# Spectacle_LED_Control_Board.net
KiCad netlist of a schematic drawn in EAGLE
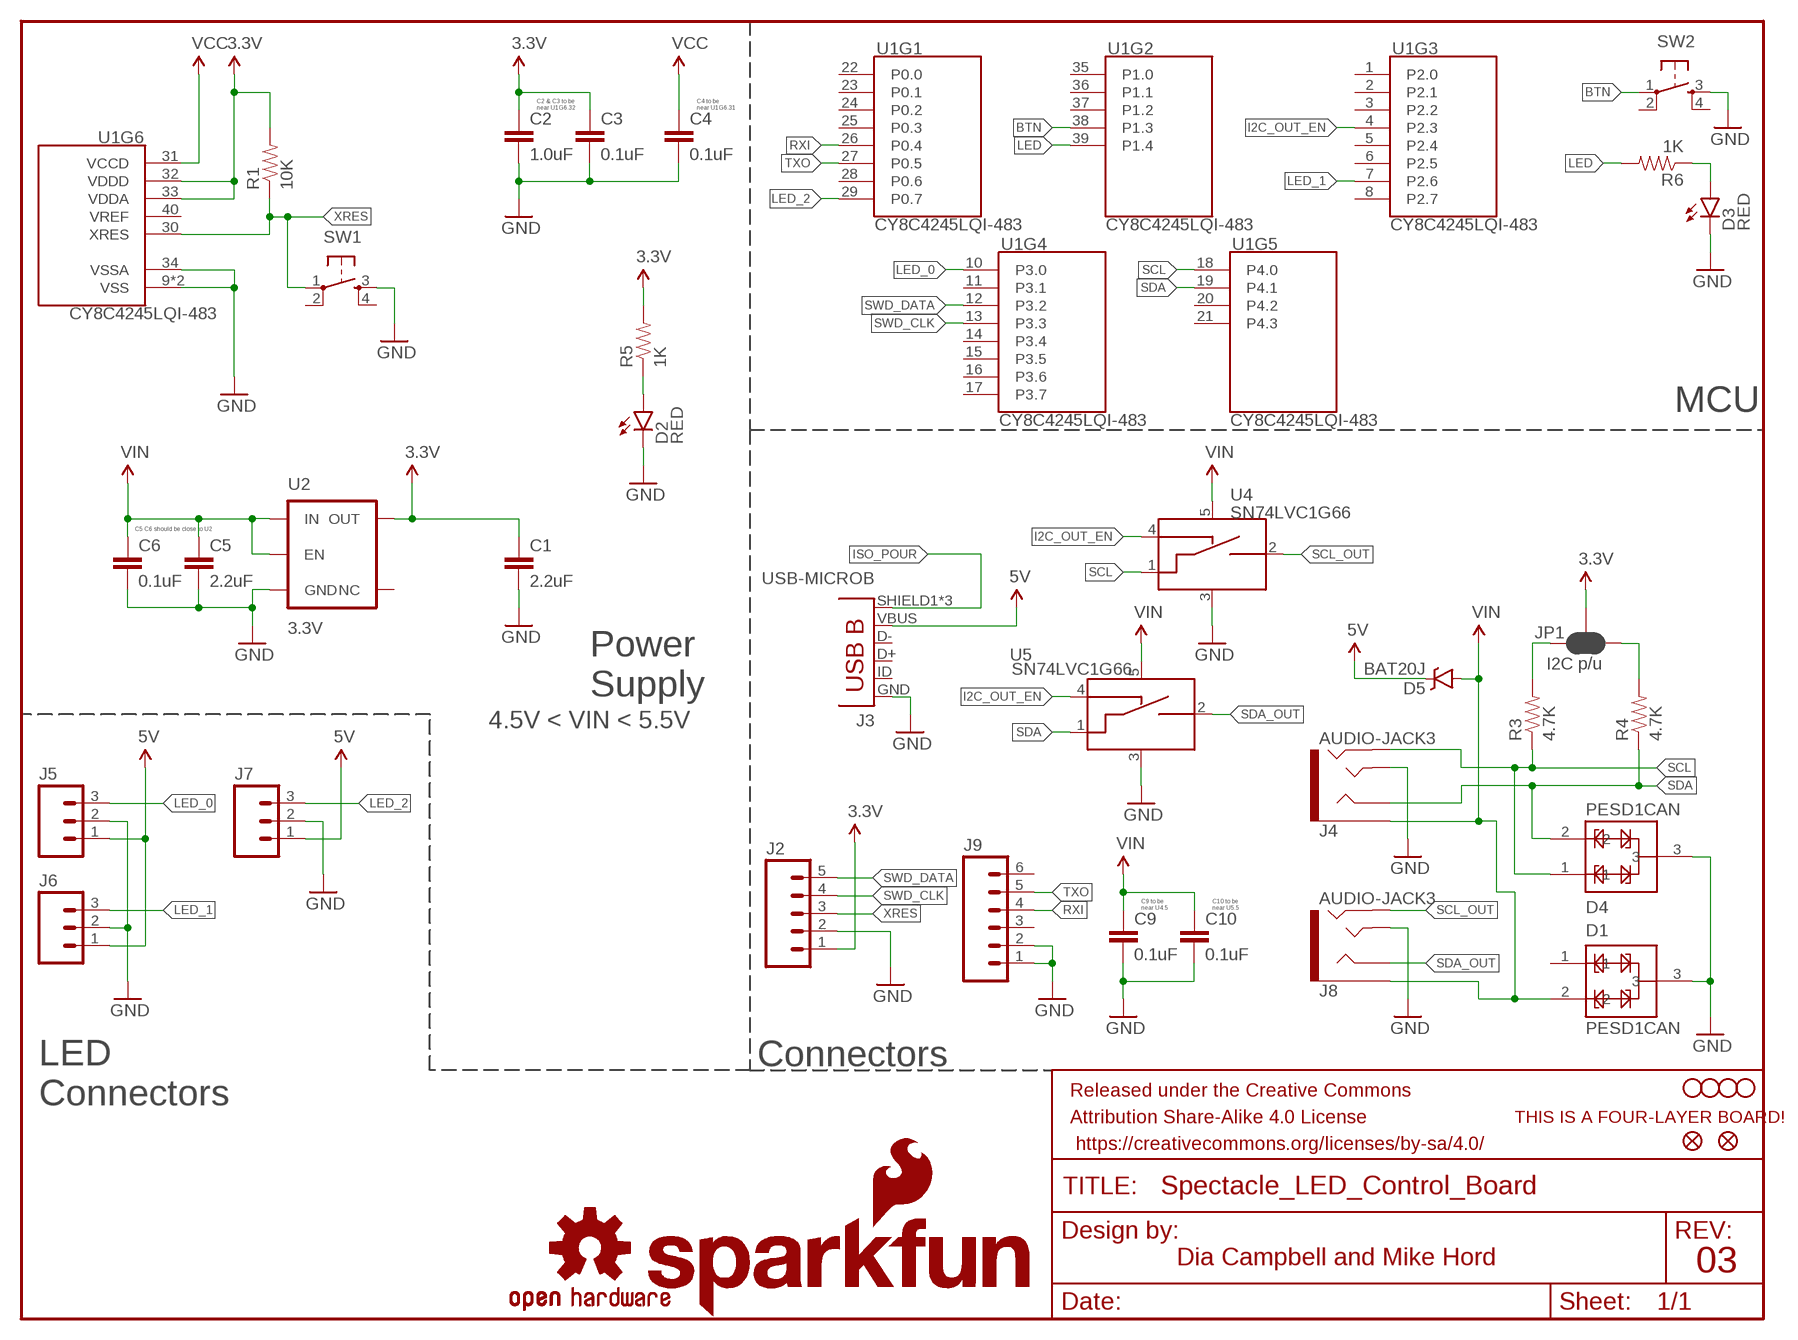
[diagram p0: schematic, sheet 1]

(export (version "E")
  (design (tool "Eeschema 10.0.6"))
  (components
    (comp (ref "C1")
      (value "2.2uF")
      (footprint "eagle-import:0603-CAP")
      (libsource (lib "eagle-import") (part "2.2UF-10V-20%(0603)"))
    )
    (comp (ref "C2")
      (value "1.0uF")
      (footprint "eagle-import:0402-CAP")
      (libsource (lib "eagle-import") (part "1.0UF-16V-10%(0402)"))
    )
    (comp (ref "C3")
      (value "0.1uF")
      (footprint "eagle-import:0402-CAP")
      (libsource (lib "eagle-import") (part "0.1UF-16V(+-10%)(0402)"))
    )
    (comp (ref "C4")
      (value "0.1uF")
      (footprint "eagle-import:0402-CAP")
      (libsource (lib "eagle-import") (part "0.1UF-16V(+-10%)(0402)"))
    )
    (comp (ref "C5")
      (value "2.2uF")
      (footprint "eagle-import:0603-CAP")
      (libsource (lib "eagle-import") (part "2.2UF-10V-20%(0603)"))
    )
    (comp (ref "C6")
      (value "0.1uF")
      (footprint "eagle-import:0402-CAP")
      (libsource (lib "eagle-import") (part "0.1UF-16V(+-10%)(0402)"))
    )
    (comp (ref "C9")
      (value "0.1uF")
      (footprint "eagle-import:0402-CAP")
      (libsource (lib "eagle-import") (part "0.1UF-16V(+-10%)(0402)"))
    )
    (comp (ref "C10")
      (value "0.1uF")
      (footprint "eagle-import:0402-CAP")
      (libsource (lib "eagle-import") (part "0.1UF-16V(+-10%)(0402)"))
    )
    (comp (ref "D1")
      (value "PESD1CAN")
      (footprint "eagle-import:SOT23-3")
      (libsource (lib "eagle-import") (part "PESD1CAN"))
    )
    (comp (ref "D2")
      (value "RED")
      (footprint "eagle-import:LED-0603")
      (libsource (lib "eagle-import") (part "LED-RED0603"))
    )
    (comp (ref "D3")
      (value "RED")
      (footprint "eagle-import:LED-0603")
      (libsource (lib "eagle-import") (part "LED-RED0603"))
    )
    (comp (ref "D4")
      (value "PESD1CAN")
      (footprint "eagle-import:SOT23-3")
      (libsource (lib "eagle-import") (part "PESD1CAN"))
    )
    (comp (ref "D5")
      (value "BAT20J")
      (footprint "eagle-import:SOD-323")
      (libsource (lib "eagle-import") (part "DIODE-SCHOTTKY-BAT20J"))
    )
    (comp (ref "FD1")
      (value "FIDUCIALUFIDUCIAL")
      (footprint "eagle-import:MICRO-FIDUCIAL")
      (libsource (lib "eagle-import") (part "FIDUCIALUFIDUCIAL"))
    )
    (comp (ref "FD2")
      (value "FIDUCIALUFIDUCIAL")
      (footprint "eagle-import:MICRO-FIDUCIAL")
      (libsource (lib "eagle-import") (part "FIDUCIALUFIDUCIAL"))
    )
    (comp (ref "FRAME1")
      (value "FRAME-LETTER")
      (footprint "eagle-import:CREATIVE_COMMONS")
      (libsource (lib "eagle-import") (part "FRAME-LETTER"))
    )
    (comp (ref "H1")
      (value "STAND-OFF")
      (footprint "eagle-import:STAND-OFF")
      (libsource (lib "eagle-import") (part "STAND-OFF"))
    )
    (comp (ref "H2")
      (value "STAND-OFF")
      (footprint "eagle-import:STAND-OFF")
      (libsource (lib "eagle-import") (part "STAND-OFF"))
    )
    (comp (ref "H3")
      (value "STAND-OFF")
      (footprint "eagle-import:STAND-OFF")
      (libsource (lib "eagle-import") (part "STAND-OFF"))
    )
    (comp (ref "H4")
      (value "STAND-OFF")
      (footprint "eagle-import:STAND-OFF")
      (libsource (lib "eagle-import") (part "STAND-OFF"))
    )
    (comp (ref "J2")
      (value "M05NO_SILK")
      (footprint "eagle-import:1X05_NO_SILK")
      (libsource (lib "eagle-import") (part "M05NO_SILK"))
    )
    (comp (ref "J3")
      (value "USB-MICROB")
      (footprint "eagle-import:USB-B-MICRO-SMD_V03")
      (libsource (lib "eagle-import") (part "USB-MICROB{dblquote}"))
    )
    (comp (ref "J4")
      (value "AUDIO-JACK3")
      (footprint "eagle-import:AUDIO-JACK-TRRS-SMD")
      (libsource (lib "eagle-import") (part "AUDIO-JACK3"))
    )
    (comp (ref "J5")
      (value "M03JST-PTH-VERT")
      (footprint "eagle-import:JST-3-PTH-VERT")
      (libsource (lib "eagle-import") (part "M03JST-PTH-VERT"))
    )
    (comp (ref "J6")
      (value "M03JST-PTH-VERT")
      (footprint "eagle-import:JST-3-PTH-VERT")
      (libsource (lib "eagle-import") (part "M03JST-PTH-VERT"))
    )
    (comp (ref "J7")
      (value "M03JST-PTH-VERT")
      (footprint "eagle-import:JST-3-PTH-VERT")
      (libsource (lib "eagle-import") (part "M03JST-PTH-VERT"))
    )
    (comp (ref "J8")
      (value "AUDIO-JACK3")
      (footprint "eagle-import:AUDIO-JACK-TRRS-SMD")
      (libsource (lib "eagle-import") (part "AUDIO-JACK3"))
    )
    (comp (ref "J9")
      (value "M06NO_SILK_NO_POP")
      (footprint "eagle-import:1X06_NO_SILK")
      (libsource (lib "eagle-import") (part "M06NO_SILK_NO_POP"))
    )
    (comp (ref "JP1")
      (value "JUMPER-PAD-3-NC_BY_PASTE")
      (footprint "eagle-import:PAD-JUMPER-3-NC_BY_PASTE_YES_SILK_FULL_BOX")
      (libsource (lib "eagle-import") (part "JUMPER-PAD-3-NC_BY_PASTE"))
    )
    (comp (ref "LOGO1")
      (value "OSHW-LOGOS")
      (footprint "eagle-import:OSHW-LOGO-S")
      (libsource (lib "eagle-import") (part "OSHW-LOGOS"))
    )
    (comp (ref "LOGO2")
      (value "SFE_LOGO_NAME_FLAME.1_INCH")
      (footprint "eagle-import:SFE_LOGO_NAME_FLAME_.1")
      (libsource (lib "eagle-import") (part "SFE_LOGO_NAME_FLAME.1_INCH"))
    )
    (comp (ref "R1")
      (value "10K")
      (footprint "eagle-import:0603-RES")
      (libsource (lib "eagle-import") (part "10KOHM-1/10W-1%(0603)0603"))
    )
    (comp (ref "R3")
      (value "4.7K")
      (footprint "eagle-import:0603-RES")
      (libsource (lib "eagle-import") (part "4.7KOHM-1/10W-1%(0603)"))
    )
    (comp (ref "R4")
      (value "4.7K")
      (footprint "eagle-import:0603-RES")
      (libsource (lib "eagle-import") (part "4.7KOHM-1/10W-1%(0603)"))
    )
    (comp (ref "R5")
      (value "1K")
      (footprint "eagle-import:0603-RES")
      (libsource (lib "eagle-import") (part "1KOHM-1/10W-1%(0603)"))
    )
    (comp (ref "R6")
      (value "1K")
      (footprint "eagle-import:0603-RES")
      (libsource (lib "eagle-import") (part "1KOHM-1/10W-1%(0603)"))
    )
    (comp (ref "SW1")
      (value "SWITCH_SPST_4_PINRECT")
      (footprint "eagle-import:TACTILE_SWITCH_SMD_4.6X2.8MM")
      (libsource (lib "eagle-import") (part "SWITCH_SPST_4_PINRECT"))
    )
    (comp (ref "SW2")
      (value "SWITCH_SPST_4_PINRECT")
      (footprint "eagle-import:TACTILE_SWITCH_SMD_4.6X2.8MM")
      (libsource (lib "eagle-import") (part "SWITCH_SPST_4_PINRECT"))
    )
    (comp (ref "U$1")
      (value "FOUR_LAYER_WARNING")
      (footprint "eagle-import:FOUR_LAYER_WARNING")
      (libsource (lib "eagle-import") (part "FOUR_LAYER_WARNING"))
    )
    (comp (ref "U1")
      (value "CY8C4245LQI-483")
      (footprint "eagle-import:QFN-40")
      (libsource (lib "eagle-import") (part "PSOC4_4200_40QFN"))
    )
    (comp (ref "U2")
      (value "3.3V")
      (footprint "eagle-import:SOT23-5")
      (libsource (lib "eagle-import") (part "V_REG_AP2112K-3.3V"))
    )
    (comp (ref "U4")
      (value "SN74LVC1G66")
      (footprint "eagle-import:SOT23-5")
      (libsource (lib "eagle-import") (part "SN74LVC1G66_SPST_AMUX"))
    )
    (comp (ref "U5")
      (value "SN74LVC1G66")
      (footprint "eagle-import:SOT23-5")
      (libsource (lib "eagle-import") (part "SN74LVC1G66_SPST_AMUX"))
    )
  )
  (nets
    (net (code "1") (name "3.3V") (class "Default")
      (node (ref "C1") (pin "1") (pinfunction "1_1") (pintype "passive"))
      (node (ref "C2") (pin "1") (pinfunction "1_1") (pintype "passive"))
      (node (ref "C3") (pin "1") (pinfunction "1_1") (pintype "passive"))
      (node (ref "J2") (pin "1") (pinfunction "1_1") (pintype "passive"))
      (node (ref "JP1") (pin "2") (pinfunction "2_2") (pintype "passive"))
      (node (ref "R1") (pin "2") (pinfunction "2_2") (pintype "passive"))
      (node (ref "R5") (pin "2") (pinfunction "2_2") (pintype "passive"))
      (node (ref "U1") (pin "32") (pinfunction "VDDD_32") (pintype "bidirectional"))
      (node (ref "U1") (pin "33") (pinfunction "VDDA_33") (pintype "bidirectional"))
      (node (ref "U2") (pin "5") (pinfunction "OUT_5") (pintype "passive"))
    )
    (net (code "2") (name "5V") (class "Default")
      (node (ref "D5") (pin "C") (pinfunction "C_C") (pintype "passive"))
      (node (ref "J3") (pin "VBUS") (pinfunction "VBUS_VBUS") (pintype "bidirectional"))
      (node (ref "J5") (pin "1") (pinfunction "1_1") (pintype "passive"))
      (node (ref "J6") (pin "1") (pinfunction "1_1") (pintype "passive"))
      (node (ref "J7") (pin "1") (pinfunction "1_1") (pintype "passive"))
    )
    (net (code "3") (name "BTN") (class "Default")
      (node (ref "SW2") (pin "1") (pinfunction "1_1") (pintype "passive"))
      (node (ref "U1") (pin "38") (pinfunction "P1.3_38") (pintype "bidirectional"))
    )
    (net (code "4") (name "GND") (class "Default")
      (node (ref "C1") (pin "2") (pinfunction "2_2") (pintype "passive"))
      (node (ref "C10") (pin "2") (pinfunction "2_2") (pintype "passive"))
      (node (ref "C2") (pin "2") (pinfunction "2_2") (pintype "passive"))
      (node (ref "C3") (pin "2") (pinfunction "2_2") (pintype "passive"))
      (node (ref "C4") (pin "2") (pinfunction "2_2") (pintype "passive"))
      (node (ref "C5") (pin "2") (pinfunction "2_2") (pintype "passive"))
      (node (ref "C6") (pin "2") (pinfunction "2_2") (pintype "passive"))
      (node (ref "C9") (pin "2") (pinfunction "2_2") (pintype "passive"))
      (node (ref "D1") (pin "3") (pinfunction "3_3") (pintype "bidirectional"))
      (node (ref "D2") (pin "C") (pinfunction "C_C") (pintype "passive"))
      (node (ref "D3") (pin "C") (pinfunction "C_C") (pintype "passive"))
      (node (ref "D4") (pin "3") (pinfunction "3_3") (pintype "bidirectional"))
      (node (ref "J2") (pin "2") (pinfunction "2_2") (pintype "passive"))
      (node (ref "J3") (pin "GND") (pinfunction "GND_GND") (pintype "bidirectional"))
      (node (ref "J4") (pin "TIP") (pinfunction "TIP_TIP") (pintype "bidirectional"))
      (node (ref "J5") (pin "2") (pinfunction "2_2") (pintype "passive"))
      (node (ref "J6") (pin "2") (pinfunction "2_2") (pintype "passive"))
      (node (ref "J7") (pin "2") (pinfunction "2_2") (pintype "passive"))
      (node (ref "J8") (pin "TIP") (pinfunction "TIP_TIP") (pintype "bidirectional"))
      (node (ref "J9") (pin "1") (pinfunction "1_1") (pintype "passive"))
      (node (ref "J9") (pin "2") (pinfunction "2_2") (pintype "passive"))
      (node (ref "SW1") (pin "3") (pinfunction "3_3") (pintype "passive"))
      (node (ref "SW2") (pin "3") (pinfunction "3_3") (pintype "passive"))
      (node (ref "U1") (pin "34") (pinfunction "VSSA_34") (pintype "bidirectional"))
      (node (ref "U1") (pin "9") (pinfunction "VSS_9") (pintype "bidirectional"))
      (node (ref "U1") (pin "EP") (pinfunction "VSS_EP") (pintype "bidirectional"))
      (node (ref "U2") (pin "2") (pinfunction "GND_2") (pintype "input"))
      (node (ref "U4") (pin "3") (pinfunction "VSS_3") (pintype "bidirectional"))
      (node (ref "U5") (pin "3") (pinfunction "VSS_3") (pintype "bidirectional"))
    )
    (net (code "5") (name "I2C_OUT_EN") (class "Default")
      (node (ref "U1") (pin "4") (pinfunction "P2.3_4") (pintype "bidirectional"))
      (node (ref "U4") (pin "4") (pinfunction "CTRL_IN_4") (pintype "bidirectional"))
      (node (ref "U5") (pin "4") (pinfunction "CTRL_IN_4") (pintype "bidirectional"))
    )
    (net (code "6") (name "ISO_POUR") (class "Default")
      (node (ref "J3") (pin "SHIELD1") (pinfunction "SHIELD_SHIELD1") (pintype "bidirectional"))
      (node (ref "J3") (pin "SHIELD2") (pinfunction "SHIELD_SHIELD2") (pintype "bidirectional"))
      (node (ref "J3") (pin "SHIELD3") (pinfunction "SHIELD_SHIELD3") (pintype "bidirectional"))
    )
    (net (code "7") (name "LED") (class "Default")
      (node (ref "R6") (pin "2") (pinfunction "2_2") (pintype "passive"))
      (node (ref "U1") (pin "39") (pinfunction "P1.4_39") (pintype "bidirectional"))
    )
    (net (code "8") (name "LED_0") (class "Default")
      (node (ref "J5") (pin "3") (pinfunction "3_3") (pintype "passive"))
      (node (ref "U1") (pin "10") (pinfunction "P3.0_10") (pintype "bidirectional"))
    )
    (net (code "9") (name "LED_1") (class "Default")
      (node (ref "J6") (pin "3") (pinfunction "3_3") (pintype "passive"))
      (node (ref "U1") (pin "7") (pinfunction "P2.6_7") (pintype "bidirectional"))
    )
    (net (code "10") (name "LED_2") (class "Default")
      (node (ref "J7") (pin "3") (pinfunction "3_3") (pintype "passive"))
      (node (ref "U1") (pin "29") (pinfunction "P0.7_29") (pintype "bidirectional"))
    )
    (net (code "11") (name "Net-(D2-PadA)") (class "Default")
      (node (ref "D2") (pin "A") (pinfunction "A_A") (pintype "passive"))
      (node (ref "R5") (pin "1") (pinfunction "1_1") (pintype "passive"))
    )
    (net (code "12") (name "Net-(D3-PadA)") (class "Default")
      (node (ref "D3") (pin "A") (pinfunction "A_A") (pintype "passive"))
      (node (ref "R6") (pin "1") (pinfunction "1_1") (pintype "passive"))
    )
    (net (code "13") (name "Net-(JP1-Pad1)") (class "Default")
      (node (ref "JP1") (pin "1") (pinfunction "1_1") (pintype "passive"))
      (node (ref "R4") (pin "2") (pinfunction "2_2") (pintype "passive"))
    )
    (net (code "14") (name "Net-(JP1-Pad3)") (class "Default")
      (node (ref "JP1") (pin "3") (pinfunction "3_3") (pintype "passive"))
      (node (ref "R3") (pin "2") (pinfunction "2_2") (pintype "passive"))
    )
    (net (code "15") (name "RXI") (class "Default")
      (node (ref "J9") (pin "4") (pinfunction "4_4") (pintype "passive"))
      (node (ref "U1") (pin "26") (pinfunction "P0.4_26") (pintype "bidirectional"))
    )
    (net (code "16") (name "SCL") (class "Default")
      (node (ref "D4") (pin "1") (pinfunction "1_1") (pintype "bidirectional"))
      (node (ref "J4") (pin "RING2") (pinfunction "RING2_RING2") (pintype "bidirectional"))
      (node (ref "R3") (pin "1") (pinfunction "1_1") (pintype "passive"))
      (node (ref "U1") (pin "18") (pinfunction "P4.0_18") (pintype "bidirectional"))
      (node (ref "U4") (pin "1") (pinfunction "A_IN_1") (pintype "bidirectional"))
    )
    (net (code "17") (name "SCL_OUT") (class "Default")
      (node (ref "J8") (pin "RING2") (pinfunction "RING2_RING2") (pintype "bidirectional"))
      (node (ref "U4") (pin "2") (pinfunction "A_OUT_2") (pintype "bidirectional"))
    )
    (net (code "18") (name "SDA") (class "Default")
      (node (ref "D4") (pin "2") (pinfunction "2_2") (pintype "bidirectional"))
      (node (ref "J4") (pin "RING1") (pinfunction "RING1_RING1") (pintype "bidirectional"))
      (node (ref "R4") (pin "1") (pinfunction "1_1") (pintype "passive"))
      (node (ref "U1") (pin "19") (pinfunction "P4.1_19") (pintype "bidirectional"))
      (node (ref "U5") (pin "1") (pinfunction "A_IN_1") (pintype "bidirectional"))
    )
    (net (code "19") (name "SDA_OUT") (class "Default")
      (node (ref "J8") (pin "RING1") (pinfunction "RING1_RING1") (pintype "bidirectional"))
      (node (ref "U5") (pin "2") (pinfunction "A_OUT_2") (pintype "bidirectional"))
    )
    (net (code "20") (name "SWD_CLK") (class "Default")
      (node (ref "J2") (pin "4") (pinfunction "4_4") (pintype "passive"))
      (node (ref "U1") (pin "13") (pinfunction "P3.3_13") (pintype "bidirectional"))
    )
    (net (code "21") (name "SWD_DATA") (class "Default")
      (node (ref "J2") (pin "5") (pinfunction "5_5") (pintype "passive"))
      (node (ref "U1") (pin "12") (pinfunction "P3.2_12") (pintype "bidirectional"))
    )
    (net (code "22") (name "TXO") (class "Default")
      (node (ref "J9") (pin "5") (pinfunction "5_5") (pintype "passive"))
      (node (ref "U1") (pin "27") (pinfunction "P0.5_27") (pintype "bidirectional"))
    )
    (net (code "23") (name "VCC") (class "Default")
      (node (ref "C4") (pin "1") (pinfunction "1_1") (pintype "passive"))
      (node (ref "U1") (pin "31") (pinfunction "VCCD_31") (pintype "bidirectional"))
    )
    (net (code "24") (name "VIN") (class "Default")
      (node (ref "C10") (pin "1") (pinfunction "1_1") (pintype "passive"))
      (node (ref "C5") (pin "1") (pinfunction "1_1") (pintype "passive"))
      (node (ref "C6") (pin "1") (pinfunction "1_1") (pintype "passive"))
      (node (ref "C9") (pin "1") (pinfunction "1_1") (pintype "passive"))
      (node (ref "D1") (pin "2") (pinfunction "2_2") (pintype "bidirectional"))
      (node (ref "D5") (pin "A") (pinfunction "A_A") (pintype "passive"))
      (node (ref "J4") (pin "EARTH") (pinfunction "EARTH_EARTH") (pintype "bidirectional"))
      (node (ref "J8") (pin "EARTH") (pinfunction "EARTH_EARTH") (pintype "bidirectional"))
      (node (ref "U2") (pin "1") (pinfunction "IN_1") (pintype "input"))
      (node (ref "U2") (pin "3") (pinfunction "EN_3") (pintype "input"))
      (node (ref "U4") (pin "5") (pinfunction "VCC_5") (pintype "bidirectional"))
      (node (ref "U5") (pin "5") (pinfunction "VCC_5") (pintype "bidirectional"))
    )
    (net (code "25") (name "XRES") (class "Default")
      (node (ref "J2") (pin "3") (pinfunction "3_3") (pintype "passive"))
      (node (ref "R1") (pin "1") (pinfunction "1_1") (pintype "passive"))
      (node (ref "SW1") (pin "1") (pinfunction "1_1") (pintype "passive"))
      (node (ref "U1") (pin "30") (pinfunction "XRES_30") (pintype "bidirectional"))
    )
    (net (code "26") (name "unconnected-(D1-Pad1)") (class "Default")
      (node (ref "D1") (pin "1") (pinfunction "1_1") (pintype "bidirectional"))
    )
    (net (code "27") (name "unconnected-(J3-PadD+)") (class "Default")
      (node (ref "J3") (pin "D+") (pinfunction "D+_D+") (pintype "bidirectional"))
    )
    (net (code "28") (name "unconnected-(J3-PadD-)") (class "Default")
      (node (ref "J3") (pin "D-") (pinfunction "D-_D-") (pintype "bidirectional"))
    )
    (net (code "29") (name "unconnected-(J3-USBID-PadID)") (class "Default")
      (node (ref "J3") (pin "ID") (pinfunction "USBID_ID") (pintype "bidirectional"))
    )
    (net (code "30") (name "unconnected-(J9-Pad3)") (class "Default")
      (node (ref "J9") (pin "3") (pinfunction "3_3") (pintype "passive"))
    )
    (net (code "31") (name "unconnected-(J9-Pad6)") (class "Default")
      (node (ref "J9") (pin "6") (pinfunction "6_6") (pintype "passive"))
    )
    (net (code "32") (name "unconnected-(SW1-Pad2)") (class "Default")
      (node (ref "SW1") (pin "2") (pinfunction "2_2") (pintype "passive"))
    )
    (net (code "33") (name "unconnected-(SW1-Pad4)") (class "Default")
      (node (ref "SW1") (pin "4") (pinfunction "4_4") (pintype "passive"))
    )
    (net (code "34") (name "unconnected-(SW2-Pad2)") (class "Default")
      (node (ref "SW2") (pin "2") (pinfunction "2_2") (pintype "passive"))
    )
    (net (code "35") (name "unconnected-(SW2-Pad4)") (class "Default")
      (node (ref "SW2") (pin "4") (pinfunction "4_4") (pintype "passive"))
    )
    (net (code "36") (name "unconnected-(U1A-P0.0-Pad22)") (class "Default")
      (node (ref "U1") (pin "22") (pinfunction "P0.0_22") (pintype "bidirectional"))
    )
    (net (code "37") (name "unconnected-(U1A-P0.1-Pad23)") (class "Default")
      (node (ref "U1") (pin "23") (pinfunction "P0.1_23") (pintype "bidirectional"))
    )
    (net (code "38") (name "unconnected-(U1A-P0.2-Pad24)") (class "Default")
      (node (ref "U1") (pin "24") (pinfunction "P0.2_24") (pintype "bidirectional"))
    )
    (net (code "39") (name "unconnected-(U1A-P0.3-Pad25)") (class "Default")
      (node (ref "U1") (pin "25") (pinfunction "P0.3_25") (pintype "bidirectional"))
    )
    (net (code "40") (name "unconnected-(U1A-P0.6-Pad28)") (class "Default")
      (node (ref "U1") (pin "28") (pinfunction "P0.6_28") (pintype "bidirectional"))
    )
    (net (code "41") (name "unconnected-(U1B-P1.0-Pad35)") (class "Default")
      (node (ref "U1") (pin "35") (pinfunction "P1.0_35") (pintype "bidirectional"))
    )
    (net (code "42") (name "unconnected-(U1B-P1.1-Pad36)") (class "Default")
      (node (ref "U1") (pin "36") (pinfunction "P1.1_36") (pintype "bidirectional"))
    )
    (net (code "43") (name "unconnected-(U1B-P1.2-Pad37)") (class "Default")
      (node (ref "U1") (pin "37") (pinfunction "P1.2_37") (pintype "bidirectional"))
    )
    (net (code "44") (name "unconnected-(U1C-P2.0-Pad1)") (class "Default")
      (node (ref "U1") (pin "1") (pinfunction "P2.0_1") (pintype "bidirectional"))
    )
    (net (code "45") (name "unconnected-(U1C-P2.1-Pad2)") (class "Default")
      (node (ref "U1") (pin "2") (pinfunction "P2.1_2") (pintype "bidirectional"))
    )
    (net (code "46") (name "unconnected-(U1C-P2.2-Pad3)") (class "Default")
      (node (ref "U1") (pin "3") (pinfunction "P2.2_3") (pintype "bidirectional"))
    )
    (net (code "47") (name "unconnected-(U1C-P2.4-Pad5)") (class "Default")
      (node (ref "U1") (pin "5") (pinfunction "P2.4_5") (pintype "bidirectional"))
    )
    (net (code "48") (name "unconnected-(U1C-P2.5-Pad6)") (class "Default")
      (node (ref "U1") (pin "6") (pinfunction "P2.5_6") (pintype "bidirectional"))
    )
    (net (code "49") (name "unconnected-(U1C-P2.7-Pad8)") (class "Default")
      (node (ref "U1") (pin "8") (pinfunction "P2.7_8") (pintype "bidirectional"))
    )
    (net (code "50") (name "unconnected-(U1D-P3.1-Pad11)") (class "Default")
      (node (ref "U1") (pin "11") (pinfunction "P3.1_11") (pintype "bidirectional"))
    )
    (net (code "51") (name "unconnected-(U1D-P3.4-Pad14)") (class "Default")
      (node (ref "U1") (pin "14") (pinfunction "P3.4_14") (pintype "bidirectional"))
    )
    (net (code "52") (name "unconnected-(U1D-P3.5-Pad15)") (class "Default")
      (node (ref "U1") (pin "15") (pinfunction "P3.5_15") (pintype "bidirectional"))
    )
    (net (code "53") (name "unconnected-(U1D-P3.6-Pad16)") (class "Default")
      (node (ref "U1") (pin "16") (pinfunction "P3.6_16") (pintype "bidirectional"))
    )
    (net (code "54") (name "unconnected-(U1D-P3.7-Pad17)") (class "Default")
      (node (ref "U1") (pin "17") (pinfunction "P3.7_17") (pintype "bidirectional"))
    )
    (net (code "55") (name "unconnected-(U1E-P4.2-Pad20)") (class "Default")
      (node (ref "U1") (pin "20") (pinfunction "P4.2_20") (pintype "bidirectional"))
    )
    (net (code "56") (name "unconnected-(U1E-P4.3-Pad21)") (class "Default")
      (node (ref "U1") (pin "21") (pinfunction "P4.3_21") (pintype "bidirectional"))
    )
    (net (code "57") (name "unconnected-(U1F-VREF-Pad40)") (class "Default")
      (node (ref "U1") (pin "40") (pinfunction "VREF_40") (pintype "bidirectional"))
    )
    (net (code "58") (name "unconnected-(U2-NC-Pad4)") (class "Default")
      (node (ref "U2") (pin "4") (pinfunction "NC_4") (pintype "input"))
    )
  )
)
